# Sweep.net
KiCad netlist of a schematic drawn in EAGLE
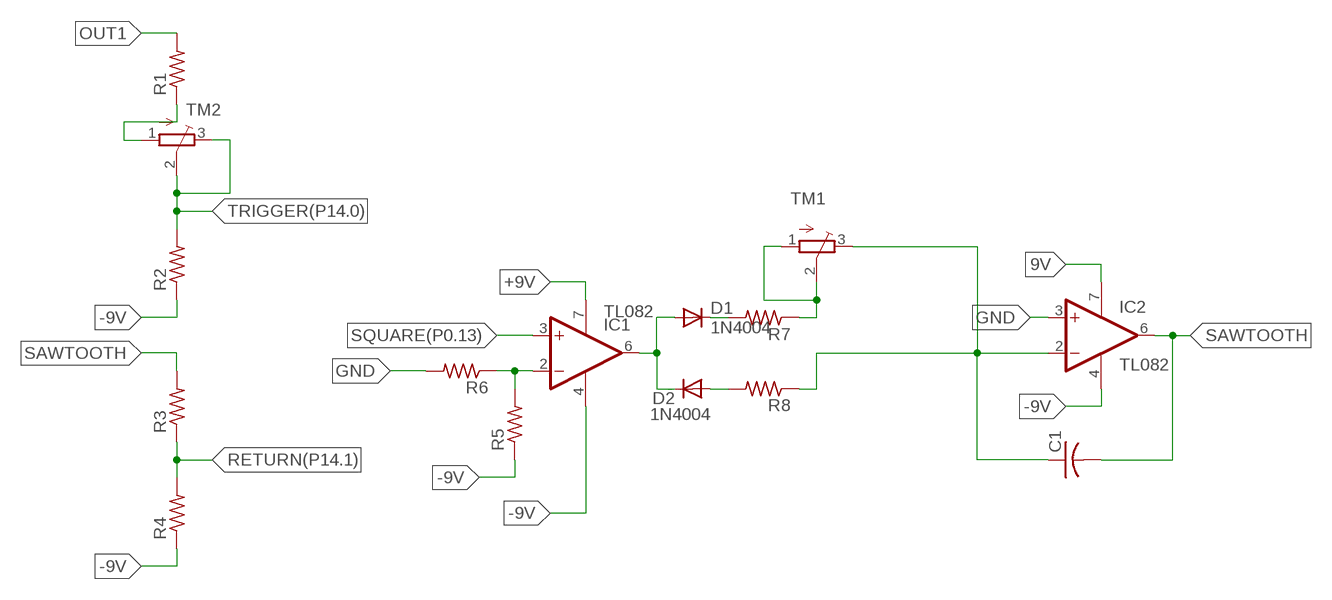
[diagram p0: schematic, sheet 1]

(export (version "E")
  (design (tool "Eeschema 10.0.6"))
  (components
    (comp (ref "C1")
      (value "C-US025-024X044")
      (footprint "eagle-import:C025-024X044")
      (libsource (lib "eagle-import") (part "C-US025-024X044"))
    )
    (comp (ref "D1")
      (value "1N4004")
      (footprint "eagle-import:DO41-10")
      (libsource (lib "eagle-import") (part "1N4004"))
    )
    (comp (ref "D2")
      (value "1N4004")
      (footprint "eagle-import:DO41-10")
      (libsource (lib "eagle-import") (part "1N4004"))
    )
    (comp (ref "IC1")
      (value "TL082")
      (footprint "eagle-import:SO08")
      (libsource (lib "eagle-import") (part "OPA333D"))
    )
    (comp (ref "IC2")
      (value "TL082")
      (footprint "eagle-import:SO08")
      (libsource (lib "eagle-import") (part "OPA333D"))
    )
    (comp (ref "R1")
      (value "R-US_0204/2V")
      (footprint "eagle-import:0204V")
      (libsource (lib "eagle-import") (part "R-US_0204/2V"))
    )
    (comp (ref "R2")
      (value "R-US_0204/2V")
      (footprint "eagle-import:0204V")
      (libsource (lib "eagle-import") (part "R-US_0204/2V"))
    )
    (comp (ref "R3")
      (value "R-US_0204/2V")
      (footprint "eagle-import:0204V")
      (libsource (lib "eagle-import") (part "R-US_0204/2V"))
    )
    (comp (ref "R4")
      (value "R-US_0204/2V")
      (footprint "eagle-import:0204V")
      (libsource (lib "eagle-import") (part "R-US_0204/2V"))
    )
    (comp (ref "R5")
      (value "R-US_0204/2V")
      (footprint "eagle-import:0204V")
      (libsource (lib "eagle-import") (part "R-US_0204/2V"))
    )
    (comp (ref "R6")
      (value "R-US_0204/2V")
      (footprint "eagle-import:0204V")
      (libsource (lib "eagle-import") (part "R-US_0204/2V"))
    )
    (comp (ref "R7")
      (value "R-US_0204/2V")
      (footprint "eagle-import:0204V")
      (libsource (lib "eagle-import") (part "R-US_0204/2V"))
    )
    (comp (ref "R8")
      (value "R-US_0204/2V")
      (footprint "eagle-import:0204V")
      (libsource (lib "eagle-import") (part "R-US_0204/2V"))
    )
    (comp (ref "TM1")
      (value "TRIMPOT3386")
      (footprint "eagle-import:TRIM-3386")
      (libsource (lib "eagle-import") (part "TRIMPOT3386"))
    )
    (comp (ref "TM2")
      (value "TRIMPOT3386")
      (footprint "eagle-import:TRIM-3386")
      (libsource (lib "eagle-import") (part "TRIMPOT3386"))
    )
  )
  (nets
    (net (code "1") (name "+9V") (class "Default")
      (node (ref "IC1") (pin "7") (pinfunction "V+_7") (pintype "power_in"))
    )
    (net (code "2") (name "-9V") (class "Default")
      (node (ref "IC1") (pin "4") (pinfunction "V-_4") (pintype "power_in"))
      (node (ref "IC2") (pin "4") (pinfunction "V-_4") (pintype "power_in"))
      (node (ref "R2") (pin "1") (pinfunction "1_1") (pintype "passive"))
      (node (ref "R4") (pin "1") (pinfunction "1_1") (pintype "passive"))
      (node (ref "R5") (pin "1") (pinfunction "1_1") (pintype "passive"))
    )
    (net (code "3") (name "9V") (class "Default")
      (node (ref "IC2") (pin "7") (pinfunction "V+_7") (pintype "power_in"))
    )
    (net (code "4") (name "GND") (class "Default")
      (node (ref "IC2") (pin "3") (pinfunction "+IN_3") (pintype "input"))
      (node (ref "R6") (pin "2") (pinfunction "2_2") (pintype "passive"))
    )
    (net (code "5") (name "Net-(D1-PadC)") (class "Default")
      (node (ref "D1") (pin "C") (pinfunction "C_C") (pintype "passive"))
      (node (ref "R7") (pin "2") (pinfunction "2_2") (pintype "passive"))
    )
    (net (code "6") (name "Net-(D2-PadA)") (class "Default")
      (node (ref "D2") (pin "A") (pinfunction "A_A") (pintype "passive"))
      (node (ref "R8") (pin "2") (pinfunction "2_2") (pintype "passive"))
    )
    (net (code "7") (name "Net-(IC1--IN)") (class "Default")
      (node (ref "IC1") (pin "2") (pinfunction "-IN_2") (pintype "input"))
      (node (ref "R5") (pin "2") (pinfunction "2_2") (pintype "passive"))
      (node (ref "R6") (pin "1") (pinfunction "1_1") (pintype "passive"))
    )
    (net (code "8") (name "Net-(IC1-OUT)") (class "Default")
      (node (ref "D1") (pin "A") (pinfunction "A_A") (pintype "passive"))
      (node (ref "D2") (pin "C") (pinfunction "C_C") (pintype "passive"))
      (node (ref "IC1") (pin "6") (pinfunction "OUT_6") (pintype "output"))
    )
    (net (code "9") (name "Net-(IC2--IN)") (class "Default")
      (node (ref "C1") (pin "1") (pinfunction "1_1") (pintype "passive"))
      (node (ref "IC2") (pin "2") (pinfunction "-IN_2") (pintype "input"))
      (node (ref "R8") (pin "1") (pinfunction "1_1") (pintype "passive"))
      (node (ref "TM1") (pin "3") (pinfunction "E_3") (pintype "passive"))
    )
    (net (code "10") (name "Net-(TM1-A)") (class "Default")
      (node (ref "R7") (pin "1") (pinfunction "1_1") (pintype "passive"))
      (node (ref "TM1") (pin "1") (pinfunction "A_1") (pintype "passive"))
      (node (ref "TM1") (pin "2") (pinfunction "S_2") (pintype "passive"))
    )
    (net (code "11") (name "Net-(TM2-A)") (class "Default")
      (node (ref "R1") (pin "1") (pinfunction "1_1") (pintype "passive"))
      (node (ref "TM2") (pin "1") (pinfunction "A_1") (pintype "passive"))
    )
    (net (code "12") (name "OUT1") (class "Default")
      (node (ref "R1") (pin "2") (pinfunction "2_2") (pintype "passive"))
    )
    (net (code "13") (name "RETURN(P14.1)") (class "Default")
      (node (ref "R3") (pin "1") (pinfunction "1_1") (pintype "passive"))
      (node (ref "R4") (pin "2") (pinfunction "2_2") (pintype "passive"))
    )
    (net (code "14") (name "SAWTOOTH") (class "Default")
      (node (ref "C1") (pin "2") (pinfunction "2_2") (pintype "passive"))
      (node (ref "IC2") (pin "6") (pinfunction "OUT_6") (pintype "output"))
      (node (ref "R3") (pin "2") (pinfunction "2_2") (pintype "passive"))
    )
    (net (code "15") (name "SQUARE(P0.13)") (class "Default")
      (node (ref "IC1") (pin "3") (pinfunction "+IN_3") (pintype "input"))
    )
    (net (code "16") (name "TRIGGER(P14.0)") (class "Default")
      (node (ref "R2") (pin "2") (pinfunction "2_2") (pintype "passive"))
      (node (ref "TM2") (pin "2") (pinfunction "S_2") (pintype "passive"))
      (node (ref "TM2") (pin "3") (pinfunction "E_3") (pintype "passive"))
    )
  )
)
